# E_KEYPAD_2_2.net
KiCad netlist of a schematic drawn in EAGLE
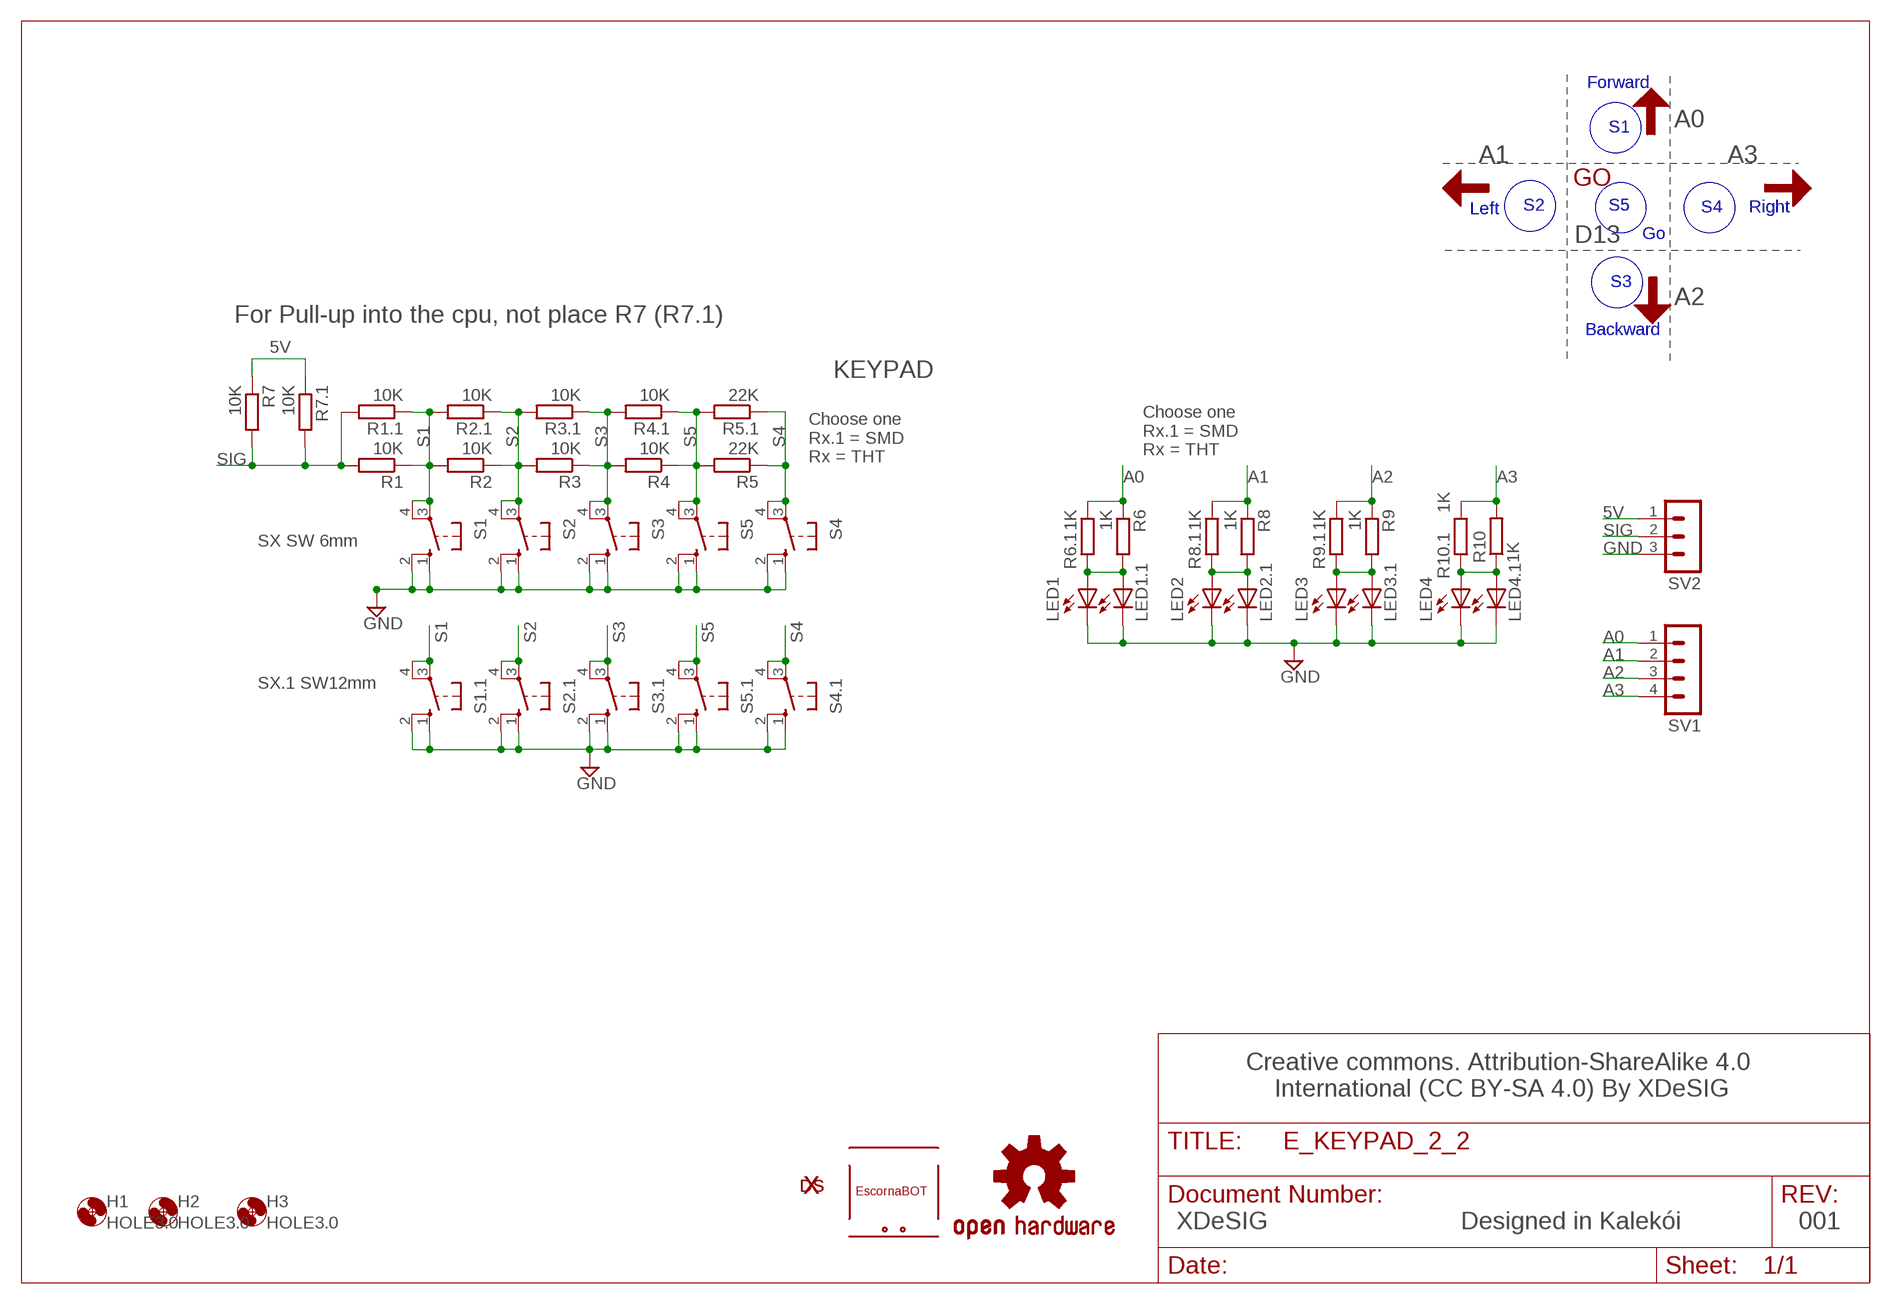
[diagram p0: schematic, sheet 1]

(export (version "E")
  (design (tool "Eeschema 10.0.6"))
  (components
    (comp (ref "H1")
      (value "HOLE3.0")
      (footprint "eagle-import:3,0")
      (libsource (lib "eagle-import") (part "MOUNT-HOLE3.0"))
    )
    (comp (ref "H2")
      (value "HOLE3.0")
      (footprint "eagle-import:3,0")
      (libsource (lib "eagle-import") (part "MOUNT-HOLE3.0"))
    )
    (comp (ref "H3")
      (value "HOLE3.0")
      (footprint "eagle-import:3,0")
      (libsource (lib "eagle-import") (part "MOUNT-HOLE3.0"))
    )
    (comp (ref "LED1")
      (value "LED3MM")
      (footprint "eagle-import:LED3MM")
      (libsource (lib "eagle-import") (part "LED3MM"))
    )
    (comp (ref "LED1.1")
      (value "LEDCHIPLED_0603")
      (footprint "eagle-import:CHIPLED_0603")
      (libsource (lib "eagle-import") (part "LEDCHIPLED_0603"))
    )
    (comp (ref "LED2")
      (value "LED3MM")
      (footprint "eagle-import:LED3MM")
      (libsource (lib "eagle-import") (part "LED3MM"))
    )
    (comp (ref "LED2.1")
      (value "LEDCHIPLED_0603")
      (footprint "eagle-import:CHIPLED_0603")
      (libsource (lib "eagle-import") (part "LEDCHIPLED_0603"))
    )
    (comp (ref "LED3")
      (value "LED3MM")
      (footprint "eagle-import:LED3MM")
      (libsource (lib "eagle-import") (part "LED3MM"))
    )
    (comp (ref "LED3.1")
      (value "LEDCHIPLED_0603")
      (footprint "eagle-import:CHIPLED_0603")
      (libsource (lib "eagle-import") (part "LEDCHIPLED_0603"))
    )
    (comp (ref "LED4")
      (value "LED3MM")
      (footprint "eagle-import:LED3MM")
      (libsource (lib "eagle-import") (part "LED3MM"))
    )
    (comp (ref "LED4.1")
      (value "LEDCHIPLED_0603")
      (footprint "eagle-import:CHIPLED_0603")
      (libsource (lib "eagle-import") (part "LEDCHIPLED_0603"))
    )
    (comp (ref "LOGO2")
      (value "OSHW-LOGOS")
      (footprint "eagle-import:OSHW-LOGO-S")
      (libsource (lib "eagle-import") (part "OSHW-LOGOS"))
    )
    (comp (ref "R1")
      (value "10K")
      (footprint "eagle-import:0204_7")
      (libsource (lib "eagle-import") (part "R-EU_0204/7"))
    )
    (comp (ref "R1.1")
      (value "10K")
      (footprint "eagle-import:R0603")
      (libsource (lib "eagle-import") (part "R-EU_R0603"))
    )
    (comp (ref "R2")
      (value "10K")
      (footprint "eagle-import:0204_7")
      (libsource (lib "eagle-import") (part "R-EU_0204/7"))
    )
    (comp (ref "R2.1")
      (value "10K")
      (footprint "eagle-import:R0603")
      (libsource (lib "eagle-import") (part "R-EU_R0603"))
    )
    (comp (ref "R3")
      (value "10K")
      (footprint "eagle-import:0204_7")
      (libsource (lib "eagle-import") (part "R-EU_0204/7"))
    )
    (comp (ref "R3.1")
      (value "10K")
      (footprint "eagle-import:R0603")
      (libsource (lib "eagle-import") (part "R-EU_R0603"))
    )
    (comp (ref "R4")
      (value "10K")
      (footprint "eagle-import:0204_7")
      (libsource (lib "eagle-import") (part "R-EU_0204/7"))
    )
    (comp (ref "R4.1")
      (value "10K")
      (footprint "eagle-import:R0603")
      (libsource (lib "eagle-import") (part "R-EU_R0603"))
    )
    (comp (ref "R5")
      (value "22K")
      (footprint "eagle-import:0204_7")
      (libsource (lib "eagle-import") (part "R-EU_0204/7"))
    )
    (comp (ref "R5.1")
      (value "22K")
      (footprint "eagle-import:R0603")
      (libsource (lib "eagle-import") (part "R-EU_R0603"))
    )
    (comp (ref "R6")
      (value "1K")
      (footprint "eagle-import:0204_7")
      (libsource (lib "eagle-import") (part "R-EU_0204/7"))
    )
    (comp (ref "R6.1")
      (value "1K")
      (footprint "eagle-import:R0603")
      (libsource (lib "eagle-import") (part "R-EU_R0603"))
    )
    (comp (ref "R7")
      (value "10K")
      (footprint "eagle-import:0204_7")
      (libsource (lib "eagle-import") (part "R-EU_0204/7"))
    )
    (comp (ref "R7.1")
      (value "10K")
      (footprint "eagle-import:R0603")
      (libsource (lib "eagle-import") (part "R-EU_R0603"))
    )
    (comp (ref "R8")
      (value "1K")
      (footprint "eagle-import:0204_7")
      (libsource (lib "eagle-import") (part "R-EU_0204/7"))
    )
    (comp (ref "R8.1")
      (value "1K")
      (footprint "eagle-import:R0603")
      (libsource (lib "eagle-import") (part "R-EU_R0603"))
    )
    (comp (ref "R9")
      (value "1K")
      (footprint "eagle-import:0204_7")
      (libsource (lib "eagle-import") (part "R-EU_0204/7"))
    )
    (comp (ref "R9.1")
      (value "1K")
      (footprint "eagle-import:R0603")
      (libsource (lib "eagle-import") (part "R-EU_R0603"))
    )
    (comp (ref "R10")
      (value "1K")
      (footprint "eagle-import:0204_7")
      (libsource (lib "eagle-import") (part "R-EU_0204/7"))
    )
    (comp (ref "R10.1")
      (value "1K")
      (footprint "eagle-import:R0603")
      (libsource (lib "eagle-import") (part "R-EU_R0603"))
    )
    (comp (ref "S1")
      (value "10-XX")
      (footprint "eagle-import:B3F-10XX")
      (fields (field (name "MPN") "B3F-1000"))
      (libsource (lib "eagle-import") (part "10-XX"))
    )
    (comp (ref "S1.1")
      (value "40-XX")
      (footprint "eagle-import:B3F-40XX")
      (fields (field (name "MF") "OMRON COMPONENTS USA") (field (name "MPN") "B3F-4000"))
      (libsource (lib "eagle-import") (part "40-XX"))
    )
    (comp (ref "S2")
      (value "10-XX")
      (footprint "eagle-import:B3F-10XX")
      (fields (field (name "MPN") "B3F-1000"))
      (libsource (lib "eagle-import") (part "10-XX"))
    )
    (comp (ref "S2.1")
      (value "40-XX")
      (footprint "eagle-import:B3F-40XX")
      (fields (field (name "MF") "OMRON COMPONENTS USA") (field (name "MPN") "B3F-4000"))
      (libsource (lib "eagle-import") (part "40-XX"))
    )
    (comp (ref "S3")
      (value "10-XX")
      (footprint "eagle-import:B3F-10XX")
      (fields (field (name "MPN") "B3F-1000"))
      (libsource (lib "eagle-import") (part "10-XX"))
    )
    (comp (ref "S3.1")
      (value "40-XX")
      (footprint "eagle-import:B3F-40XX")
      (fields (field (name "MF") "OMRON COMPONENTS USA") (field (name "MPN") "B3F-4000"))
      (libsource (lib "eagle-import") (part "40-XX"))
    )
    (comp (ref "S4")
      (value "10-XX")
      (footprint "eagle-import:B3F-10XX")
      (fields (field (name "MPN") "B3F-1000"))
      (libsource (lib "eagle-import") (part "10-XX"))
    )
    (comp (ref "S4.1")
      (value "40-XX")
      (footprint "eagle-import:B3F-40XX")
      (fields (field (name "MF") "OMRON COMPONENTS USA") (field (name "MPN") "B3F-4000"))
      (libsource (lib "eagle-import") (part "40-XX"))
    )
    (comp (ref "S5")
      (value "10-XX")
      (footprint "eagle-import:B3F-10XX")
      (fields (field (name "MPN") "B3F-1000"))
      (libsource (lib "eagle-import") (part "10-XX"))
    )
    (comp (ref "S5.1")
      (value "40-XX")
      (footprint "eagle-import:B3F-40XX")
      (fields (field (name "MF") "OMRON COMPONENTS USA") (field (name "MPN") "B3F-4000"))
      (libsource (lib "eagle-import") (part "40-XX"))
    )
    (comp (ref "SV1")
      (value "MA04-1")
      (footprint "eagle-import:MA04-1")
      (libsource (lib "eagle-import") (part "MA04-1"))
    )
    (comp (ref "SV2")
      (value "MA03-1")
      (footprint "eagle-import:MA03-1")
      (libsource (lib "eagle-import") (part "MA03-1"))
    )
    (comp (ref "U$1")
      (value "ESCORNABOT")
      (footprint "eagle-import:ESCORNA_PEQUE")
      (libsource (lib "eagle-import") (part "ESCORNABOT"))
    )
    (comp (ref "U$3")
      (value "FRECHA")
      (footprint "eagle-import:FRECHA")
      (libsource (lib "eagle-import") (part "FRECHA"))
    )
    (comp (ref "U$4")
      (value "FRECHA")
      (footprint "eagle-import:FRECHA")
      (libsource (lib "eagle-import") (part "FRECHA"))
    )
    (comp (ref "U$5")
      (value "GO")
      (footprint "eagle-import:VALE")
      (libsource (lib "eagle-import") (part "GO"))
    )
    (comp (ref "U$6")
      (value "FRECHA")
      (footprint "eagle-import:FRECHA")
      (libsource (lib "eagle-import") (part "FRECHA"))
    )
    (comp (ref "U$7")
      (value "XDESIG21")
      (footprint "eagle-import:XDESIG")
      (libsource (lib "eagle-import") (part "XDESIG21"))
    )
    (comp (ref "U$10")
      (value "XDESIG")
      (footprint "eagle-import:XDESIG_CU_2")
      (libsource (lib "eagle-import") (part "XDESIG"))
    )
    (comp (ref "U$11")
      (value "FRECHA")
      (footprint "eagle-import:FRECHA")
      (libsource (lib "eagle-import") (part "FRECHA"))
    )
  )
  (nets
    (net (code "1") (name "/5V") (class "Default")
      (node (ref "R7") (pin "1") (pinfunction "1_1") (pintype "passive"))
      (node (ref "R7.1") (pin "1") (pinfunction "1_1") (pintype "passive"))
      (node (ref "SV2") (pin "1") (pinfunction "1_1") (pintype "passive"))
    )
    (net (code "2") (name "/A0") (class "Default")
      (node (ref "R6") (pin "1") (pinfunction "1_1") (pintype "passive"))
      (node (ref "R6.1") (pin "1") (pinfunction "1_1") (pintype "passive"))
      (node (ref "SV1") (pin "1") (pinfunction "1_1") (pintype "passive"))
    )
    (net (code "3") (name "/A1") (class "Default")
      (node (ref "R8") (pin "1") (pinfunction "1_1") (pintype "passive"))
      (node (ref "R8.1") (pin "1") (pinfunction "1_1") (pintype "passive"))
      (node (ref "SV1") (pin "2") (pinfunction "2_2") (pintype "passive"))
    )
    (net (code "4") (name "/A2") (class "Default")
      (node (ref "R9") (pin "1") (pinfunction "1_1") (pintype "passive"))
      (node (ref "R9.1") (pin "1") (pinfunction "1_1") (pintype "passive"))
      (node (ref "SV1") (pin "3") (pinfunction "3_3") (pintype "passive"))
    )
    (net (code "5") (name "/A3") (class "Default")
      (node (ref "R10") (pin "2") (pinfunction "2_2") (pintype "passive"))
      (node (ref "R10.1") (pin "1") (pinfunction "1_1") (pintype "passive"))
      (node (ref "SV1") (pin "4") (pinfunction "4_4") (pintype "passive"))
    )
    (net (code "6") (name "/S1") (class "Default")
      (node (ref "R1") (pin "1") (pinfunction "1_1") (pintype "passive"))
      (node (ref "R1.1") (pin "1") (pinfunction "1_1") (pintype "passive"))
      (node (ref "R2") (pin "2") (pinfunction "2_2") (pintype "passive"))
      (node (ref "R2.1") (pin "2") (pinfunction "2_2") (pintype "passive"))
      (node (ref "S1") (pin "3") (pinfunction "P_3") (pintype "passive"))
      (node (ref "S1") (pin "4") (pinfunction "P1_4") (pintype "passive"))
      (node (ref "S1.1") (pin "3") (pinfunction "P_3") (pintype "passive"))
      (node (ref "S1.1") (pin "4") (pinfunction "P1_4") (pintype "passive"))
    )
    (net (code "7") (name "/S2") (class "Default")
      (node (ref "R2") (pin "1") (pinfunction "1_1") (pintype "passive"))
      (node (ref "R2.1") (pin "1") (pinfunction "1_1") (pintype "passive"))
      (node (ref "R3") (pin "2") (pinfunction "2_2") (pintype "passive"))
      (node (ref "R3.1") (pin "2") (pinfunction "2_2") (pintype "passive"))
      (node (ref "S2") (pin "3") (pinfunction "P_3") (pintype "passive"))
      (node (ref "S2") (pin "4") (pinfunction "P1_4") (pintype "passive"))
      (node (ref "S2.1") (pin "3") (pinfunction "P_3") (pintype "passive"))
      (node (ref "S2.1") (pin "4") (pinfunction "P1_4") (pintype "passive"))
    )
    (net (code "8") (name "/S3") (class "Default")
      (node (ref "R3") (pin "1") (pinfunction "1_1") (pintype "passive"))
      (node (ref "R3.1") (pin "1") (pinfunction "1_1") (pintype "passive"))
      (node (ref "R4") (pin "2") (pinfunction "2_2") (pintype "passive"))
      (node (ref "R4.1") (pin "2") (pinfunction "2_2") (pintype "passive"))
      (node (ref "S3") (pin "3") (pinfunction "P_3") (pintype "passive"))
      (node (ref "S3") (pin "4") (pinfunction "P1_4") (pintype "passive"))
      (node (ref "S3.1") (pin "3") (pinfunction "P_3") (pintype "passive"))
      (node (ref "S3.1") (pin "4") (pinfunction "P1_4") (pintype "passive"))
    )
    (net (code "9") (name "/S4") (class "Default")
      (node (ref "R5") (pin "1") (pinfunction "1_1") (pintype "passive"))
      (node (ref "R5.1") (pin "1") (pinfunction "1_1") (pintype "passive"))
      (node (ref "S4") (pin "3") (pinfunction "P_3") (pintype "passive"))
      (node (ref "S4") (pin "4") (pinfunction "P1_4") (pintype "passive"))
      (node (ref "S4.1") (pin "3") (pinfunction "P_3") (pintype "passive"))
      (node (ref "S4.1") (pin "4") (pinfunction "P1_4") (pintype "passive"))
    )
    (net (code "10") (name "/S5") (class "Default")
      (node (ref "R4") (pin "1") (pinfunction "1_1") (pintype "passive"))
      (node (ref "R4.1") (pin "1") (pinfunction "1_1") (pintype "passive"))
      (node (ref "R5") (pin "2") (pinfunction "2_2") (pintype "passive"))
      (node (ref "R5.1") (pin "2") (pinfunction "2_2") (pintype "passive"))
      (node (ref "S5") (pin "3") (pinfunction "P_3") (pintype "passive"))
      (node (ref "S5") (pin "4") (pinfunction "P1_4") (pintype "passive"))
      (node (ref "S5.1") (pin "3") (pinfunction "P_3") (pintype "passive"))
      (node (ref "S5.1") (pin "4") (pinfunction "P1_4") (pintype "passive"))
    )
    (net (code "11") (name "/SIG") (class "Default")
      (node (ref "R1") (pin "2") (pinfunction "2_2") (pintype "passive"))
      (node (ref "R1.1") (pin "2") (pinfunction "2_2") (pintype "passive"))
      (node (ref "R7") (pin "2") (pinfunction "2_2") (pintype "passive"))
      (node (ref "R7.1") (pin "2") (pinfunction "2_2") (pintype "passive"))
      (node (ref "SV2") (pin "2") (pinfunction "2_2") (pintype "passive"))
    )
    (net (code "12") (name "GND") (class "Default")
      (node (ref "LED1") (pin "K") (pinfunction "C_K") (pintype "passive"))
      (node (ref "LED1.1") (pin "C") (pinfunction "C_C") (pintype "passive"))
      (node (ref "LED2") (pin "K") (pinfunction "C_K") (pintype "passive"))
      (node (ref "LED2.1") (pin "C") (pinfunction "C_C") (pintype "passive"))
      (node (ref "LED3") (pin "K") (pinfunction "C_K") (pintype "passive"))
      (node (ref "LED3.1") (pin "C") (pinfunction "C_C") (pintype "passive"))
      (node (ref "LED4") (pin "K") (pinfunction "C_K") (pintype "passive"))
      (node (ref "LED4.1") (pin "C") (pinfunction "C_C") (pintype "passive"))
      (node (ref "S1") (pin "1") (pinfunction "S_1") (pintype "passive"))
      (node (ref "S1") (pin "2") (pinfunction "S1_2") (pintype "passive"))
      (node (ref "S1.1") (pin "1") (pinfunction "S_1") (pintype "passive"))
      (node (ref "S1.1") (pin "2") (pinfunction "S1_2") (pintype "passive"))
      (node (ref "S2") (pin "1") (pinfunction "S_1") (pintype "passive"))
      (node (ref "S2") (pin "2") (pinfunction "S1_2") (pintype "passive"))
      (node (ref "S2.1") (pin "1") (pinfunction "S_1") (pintype "passive"))
      (node (ref "S2.1") (pin "2") (pinfunction "S1_2") (pintype "passive"))
      (node (ref "S3") (pin "1") (pinfunction "S_1") (pintype "passive"))
      (node (ref "S3") (pin "2") (pinfunction "S1_2") (pintype "passive"))
      (node (ref "S3.1") (pin "1") (pinfunction "S_1") (pintype "passive"))
      (node (ref "S3.1") (pin "2") (pinfunction "S1_2") (pintype "passive"))
      (node (ref "S4") (pin "1") (pinfunction "S_1") (pintype "passive"))
      (node (ref "S4") (pin "2") (pinfunction "S1_2") (pintype "passive"))
      (node (ref "S4.1") (pin "1") (pinfunction "S_1") (pintype "passive"))
      (node (ref "S4.1") (pin "2") (pinfunction "S1_2") (pintype "passive"))
      (node (ref "S5") (pin "1") (pinfunction "S_1") (pintype "passive"))
      (node (ref "S5") (pin "2") (pinfunction "S1_2") (pintype "passive"))
      (node (ref "S5.1") (pin "1") (pinfunction "S_1") (pintype "passive"))
      (node (ref "S5.1") (pin "2") (pinfunction "S1_2") (pintype "passive"))
      (node (ref "SV2") (pin "3") (pinfunction "3_3") (pintype "passive"))
    )
    (net (code "13") (name "Net-(LED1-PadA)") (class "Default")
      (node (ref "LED1") (pin "A") (pinfunction "A_A") (pintype "passive"))
      (node (ref "LED1.1") (pin "A") (pinfunction "A_A") (pintype "passive"))
      (node (ref "R6") (pin "2") (pinfunction "2_2") (pintype "passive"))
      (node (ref "R6.1") (pin "2") (pinfunction "2_2") (pintype "passive"))
    )
    (net (code "14") (name "Net-(LED2-PadA)") (class "Default")
      (node (ref "LED2") (pin "A") (pinfunction "A_A") (pintype "passive"))
      (node (ref "LED2.1") (pin "A") (pinfunction "A_A") (pintype "passive"))
      (node (ref "R8") (pin "2") (pinfunction "2_2") (pintype "passive"))
      (node (ref "R8.1") (pin "2") (pinfunction "2_2") (pintype "passive"))
    )
    (net (code "15") (name "Net-(LED3-PadA)") (class "Default")
      (node (ref "LED3") (pin "A") (pinfunction "A_A") (pintype "passive"))
      (node (ref "LED3.1") (pin "A") (pinfunction "A_A") (pintype "passive"))
      (node (ref "R9") (pin "2") (pinfunction "2_2") (pintype "passive"))
      (node (ref "R9.1") (pin "2") (pinfunction "2_2") (pintype "passive"))
    )
    (net (code "16") (name "Net-(LED4-PadA)") (class "Default")
      (node (ref "LED4") (pin "A") (pinfunction "A_A") (pintype "passive"))
      (node (ref "LED4.1") (pin "A") (pinfunction "A_A") (pintype "passive"))
      (node (ref "R10") (pin "1") (pinfunction "1_1") (pintype "passive"))
      (node (ref "R10.1") (pin "2") (pinfunction "2_2") (pintype "passive"))
    )
  )
)
